# pc_healthypi_move_sensor_dual_v3.net
KiCad netlist of a schematic drawn in EAGLE
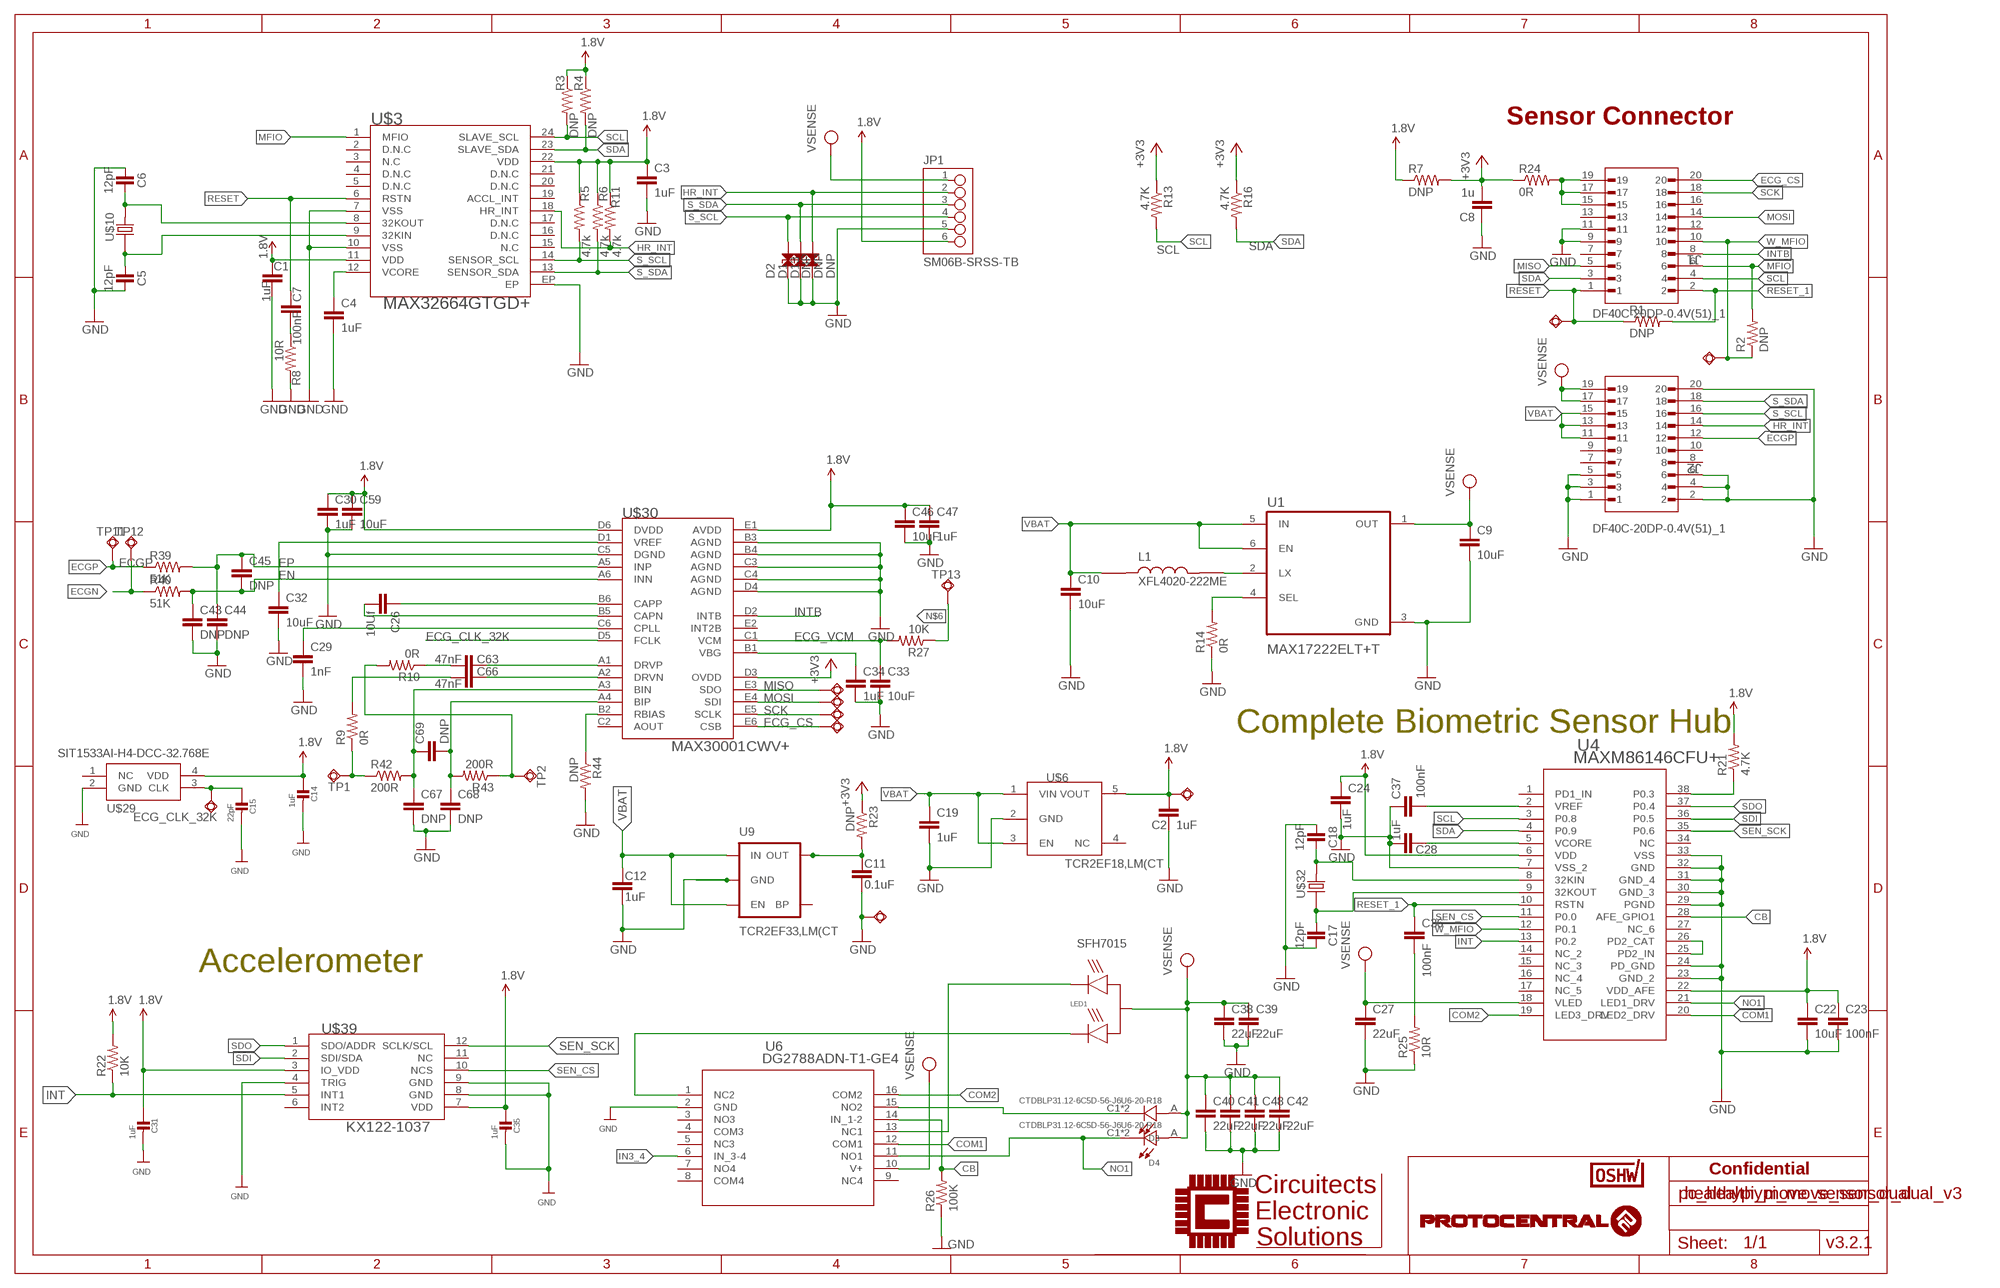
[diagram p0: schematic, sheet 1]

(export (version "E")
  (design (tool "Eeschema 10.0.6"))
  (components
    (comp (ref "C1")
      (value "1uF")
      (footprint "eagle-import:C0402")
      (libsource (lib "eagle-import") (part "C-EUC0402"))
    )
    (comp (ref "C2")
      (value "1uF")
      (footprint "eagle-import:C0402")
      (libsource (lib "eagle-import") (part "C-EUC0402"))
    )
    (comp (ref "C3")
      (value "1uF")
      (footprint "eagle-import:C0402")
      (libsource (lib "eagle-import") (part "C-EUC0402"))
    )
    (comp (ref "C4")
      (value "1uF")
      (footprint "eagle-import:C0402")
      (libsource (lib "eagle-import") (part "C-EUC0402"))
    )
    (comp (ref "C5")
      (value "12pF")
      (footprint "eagle-import:C0402")
      (libsource (lib "eagle-import") (part "CAPACITORS-0402"))
    )
    (comp (ref "C6")
      (value "12pF")
      (footprint "eagle-import:C0402")
      (libsource (lib "eagle-import") (part "CAPACITORS-0402"))
    )
    (comp (ref "C7")
      (value "100nF")
      (footprint "eagle-import:C0402")
      (libsource (lib "eagle-import") (part "C-EUC0402"))
    )
    (comp (ref "C8")
      (value "1u")
      (footprint "eagle-import:C0402")
      (libsource (lib "eagle-import") (part "C-EUC0402"))
    )
    (comp (ref "C9")
      (value "10uF")
      (footprint "eagle-import:C0402")
      (libsource (lib "eagle-import") (part "C-EUC0402"))
    )
    (comp (ref "C10")
      (value "10uF")
      (footprint "eagle-import:C0402")
      (libsource (lib "eagle-import") (part "C-EUC0402"))
    )
    (comp (ref "C11")
      (value "0.1uF")
      (footprint "eagle-import:0402")
      (libsource (lib "eagle-import") (part "0.1UF-0402-16V-10%"))
    )
    (comp (ref "C12")
      (value "1uF")
      (footprint "eagle-import:0402-TIGHT")
      (libsource (lib "eagle-import") (part "0.1UF-0402T-6.3V-10%-X7R"))
    )
    (comp (ref "C14")
      (value "1uF")
      (footprint "eagle-import:0402")
      (libsource (lib "eagle-import") (part "CAP_CERAMIC0402"))
    )
    (comp (ref "C15")
      (value "22pF")
      (footprint "eagle-import:0402")
      (libsource (lib "eagle-import") (part "CAP_CERAMIC0402"))
    )
    (comp (ref "C17")
      (value "12pF")
      (footprint "eagle-import:C0402")
      (libsource (lib "eagle-import") (part "CAPACITORS-0402"))
    )
    (comp (ref "C18")
      (value "12pF")
      (footprint "eagle-import:C0402")
      (libsource (lib "eagle-import") (part "CAPACITORS-0402"))
    )
    (comp (ref "C19")
      (value "1uF")
      (footprint "eagle-import:C0402")
      (libsource (lib "eagle-import") (part "C-EUC0402"))
    )
    (comp (ref "C22")
      (value "10uF")
      (footprint "eagle-import:C0402")
      (libsource (lib "eagle-import") (part "C-EUC0402"))
    )
    (comp (ref "C23")
      (value "100nF")
      (footprint "eagle-import:C0402")
      (libsource (lib "eagle-import") (part "C-EUC0402"))
    )
    (comp (ref "C24")
      (value "1uF")
      (footprint "eagle-import:C0402")
      (libsource (lib "eagle-import") (part "C-EUC0402"))
    )
    (comp (ref "C26")
      (value "10Uf")
      (footprint "eagle-import:C0402")
      (libsource (lib "eagle-import") (part "C-EUC0402"))
    )
    (comp (ref "C27")
      (value "22uF")
      (footprint "eagle-import:C0805")
      (libsource (lib "eagle-import") (part "C-EUC0805"))
    )
    (comp (ref "C28")
      (value "1uF")
      (footprint "eagle-import:C0402")
      (libsource (lib "eagle-import") (part "C-EUC0402"))
    )
    (comp (ref "C29")
      (value "1nF")
      (footprint "eagle-import:C0402")
      (libsource (lib "eagle-import") (part "C-EUC0402"))
    )
    (comp (ref "C30")
      (value "1uF")
      (footprint "eagle-import:C0402")
      (libsource (lib "eagle-import") (part "C-EUC0402"))
    )
    (comp (ref "C31")
      (value "1uF")
      (footprint "eagle-import:0402")
      (libsource (lib "eagle-import") (part "CAP_CERAMIC0402"))
    )
    (comp (ref "C32")
      (value "10uF")
      (footprint "eagle-import:C0402")
      (libsource (lib "eagle-import") (part "C-EUC0402"))
    )
    (comp (ref "C33")
      (value "10uF")
      (footprint "eagle-import:C0402")
      (libsource (lib "eagle-import") (part "C-EUC0402"))
    )
    (comp (ref "C34")
      (value "1uF")
      (footprint "eagle-import:C0402")
      (libsource (lib "eagle-import") (part "C-EUC0402"))
    )
    (comp (ref "C35")
      (value "1uF")
      (footprint "eagle-import:0402")
      (libsource (lib "eagle-import") (part "CAP_CERAMIC0402"))
    )
    (comp (ref "C36")
      (value "100nF")
      (footprint "eagle-import:C0402")
      (libsource (lib "eagle-import") (part "C-EUC0402"))
    )
    (comp (ref "C37")
      (value "100nF")
      (footprint "eagle-import:C0402")
      (libsource (lib "eagle-import") (part "C-EUC0402"))
    )
    (comp (ref "C38")
      (value "22uF")
      (footprint "eagle-import:C0805")
      (libsource (lib "eagle-import") (part "C-EUC0805"))
    )
    (comp (ref "C39")
      (value "22uF")
      (footprint "eagle-import:C0805")
      (libsource (lib "eagle-import") (part "C-EUC0805"))
    )
    (comp (ref "C40")
      (value "22uF")
      (footprint "eagle-import:C0805")
      (libsource (lib "eagle-import") (part "C-EUC0805"))
    )
    (comp (ref "C41")
      (value "22uF")
      (footprint "eagle-import:C0805")
      (libsource (lib "eagle-import") (part "C-EUC0805"))
    )
    (comp (ref "C42")
      (value "22uF")
      (footprint "eagle-import:C0805")
      (libsource (lib "eagle-import") (part "C-EUC0805"))
    )
    (comp (ref "C43")
      (value "DNP")
      (footprint "eagle-import:C0402")
      (libsource (lib "eagle-import") (part "C-EUC0402"))
    )
    (comp (ref "C44")
      (value "DNP")
      (footprint "eagle-import:C0402")
      (libsource (lib "eagle-import") (part "C-EUC0402"))
    )
    (comp (ref "C45")
      (value "DNP")
      (footprint "eagle-import:C0402")
      (libsource (lib "eagle-import") (part "C-EUC0402"))
    )
    (comp (ref "C46")
      (value "10uF")
      (footprint "eagle-import:C0402")
      (libsource (lib "eagle-import") (part "C-EUC0402"))
    )
    (comp (ref "C47")
      (value "1uF")
      (footprint "eagle-import:C0402")
      (libsource (lib "eagle-import") (part "C-EUC0402"))
    )
    (comp (ref "C48")
      (value "22uF")
      (footprint "eagle-import:C0805")
      (libsource (lib "eagle-import") (part "C-EUC0805"))
    )
    (comp (ref "C59")
      (value "10uF")
      (footprint "eagle-import:C0402")
      (libsource (lib "eagle-import") (part "C-EUC0402"))
    )
    (comp (ref "C63")
      (value "47nF")
      (footprint "eagle-import:C0402")
      (libsource (lib "eagle-import") (part "C-EUC0402"))
    )
    (comp (ref "C66")
      (value "47nF")
      (footprint "eagle-import:C0402")
      (libsource (lib "eagle-import") (part "C-EUC0402"))
    )
    (comp (ref "C67")
      (value "DNP")
      (footprint "eagle-import:C0402")
      (libsource (lib "eagle-import") (part "C-EUC0402"))
    )
    (comp (ref "C68")
      (value "DNP")
      (footprint "eagle-import:C0402")
      (libsource (lib "eagle-import") (part "C-EUC0402"))
    )
    (comp (ref "C69")
      (value "DNP")
      (footprint "eagle-import:C0402")
      (libsource (lib "eagle-import") (part "C-EUC0402"))
    )
    (comp (ref "D1")
      (value "DNP")
      (footprint "eagle-import:0402")
      (fields
        (field (name "DIGIKEY_PART") "PESD0402-140CT-ND")
        (field (name "MOUSE_PART") "650-PESD0402-140")
      )
      (libsource (lib "eagle-import") (part "PESD0402-0402"))
    )
    (comp (ref "D2")
      (value "DNP")
      (footprint "eagle-import:0402")
      (fields
        (field (name "DIGIKEY_PART") "PESD0402-140CT-ND")
        (field (name "MOUSE_PART") "650-PESD0402-140")
      )
      (libsource (lib "eagle-import") (part "PESD0402-0402"))
    )
    (comp (ref "D3")
      (value "CTDBLP31.12-6C5D-56-J6U6-20-R18")
      (footprint "eagle-import:LED_CTDBLP31.12-6C5D-56-J6U6-20-R18")
      (fields
        (field (name "MF") "OSRAM Opto Semiconductors")
        (field (name "MP") "CT DBLP31.12-6C5D-56-J6U6-20-R18")
      )
      (libsource (lib "eagle-import") (part "CTDBLP31.12-6C5D-56-J6U6-20-R18"))
    )
    (comp (ref "D4")
      (value "CTDBLP31.12-6C5D-56-J6U6-20-R18")
      (footprint "eagle-import:LED_CTDBLP31.12-6C5D-56-J6U6-20-R18")
      (fields
        (field (name "MF") "OSRAM Opto Semiconductors")
        (field (name "MP") "CT DBLP31.12-6C5D-56-J6U6-20-R18")
      )
      (libsource (lib "eagle-import") (part "CTDBLP31.12-6C5D-56-J6U6-20-R18"))
    )
    (comp (ref "D13")
      (value "DNP")
      (footprint "eagle-import:0402")
      (fields
        (field (name "DIGIKEY_PART") "PESD0402-140CT-ND")
        (field (name "MOUSE_PART") "650-PESD0402-140")
      )
      (libsource (lib "eagle-import") (part "PESD0402-0402"))
    )
    (comp (ref "J1")
      (value "DF40C-20DP-0.4V(51)_1")
      (footprint "eagle-import:HRS_DF40C-20DP-0.4V(51)")
      (fields (field (name "MANUFACTURER") "Hirose Electric"))
      (libsource (lib "eagle-import") (part "DF40C-20DP-0.4V(51)_1"))
    )
    (comp (ref "J2")
      (value "DF40C-20DP-0.4V(51)_1")
      (footprint "eagle-import:HRS_DF40C-20DP-0.4V(51)")
      (fields (field (name "MANUFACTURER") "Hirose Electric"))
      (libsource (lib "eagle-import") (part "DF40C-20DP-0.4V(51)_1"))
    )
    (comp (ref "JP1")
      (value "SM06B-SRSS-TB")
      (footprint "eagle-import:SM06B-SRSS-TB")
      (fields (field (name "MF") "JST Sales"))
      (libsource (lib "eagle-import") (part "SM06B-SRSS-TB"))
    )
    (comp (ref "L1")
      (value "XFL4020-222ME")
      (footprint "eagle-import:IND_XFL4020-222ME")
      (fields (field (name "MF") "Coilcraft"))
      (libsource (lib "eagle-import") (part "XFL4020-222ME"))
    )
    (comp (ref "LED1")
      (value "SFH7015")
      (footprint "eagle-import:SFH7015")
      (fields (field (name "MF") "OSRAM Opto Semiconductors") (field (name "MP") "SFH 7015"))
      (libsource (lib "eagle-import") (part "SFH7015"))
    )
    (comp (ref "R1")
      (value "DNP")
      (footprint "eagle-import:0402-RES")
      (libsource (lib "eagle-import") (part "RESISTOR0402-RES"))
    )
    (comp (ref "R2")
      (value "DNP")
      (footprint "eagle-import:0402-RES")
      (libsource (lib "eagle-import") (part "RESISTOR0402-RES"))
    )
    (comp (ref "R3")
      (value "DNP")
      (footprint "eagle-import:0402-RES")
      (libsource (lib "eagle-import") (part "RESISTOR0402-RES"))
    )
    (comp (ref "R4")
      (value "DNP")
      (footprint "eagle-import:0402-RES")
      (libsource (lib "eagle-import") (part "RESISTOR0402-RES"))
    )
    (comp (ref "R5")
      (value "4.7k")
      (footprint "eagle-import:0402-RES")
      (libsource (lib "eagle-import") (part "RESISTOR0402-RES"))
    )
    (comp (ref "R6")
      (value "4.7k")
      (footprint "eagle-import:0402-RES")
      (libsource (lib "eagle-import") (part "RESISTOR0402-RES"))
    )
    (comp (ref "R7")
      (value "DNP")
      (footprint "eagle-import:0402-RES")
      (libsource (lib "eagle-import") (part "RESISTOR0402-RES"))
    )
    (comp (ref "R8")
      (value "10R")
      (footprint "eagle-import:0402-RES")
      (libsource (lib "eagle-import") (part "RESISTOR0402-RES"))
    )
    (comp (ref "R9")
      (value "0R")
      (footprint "eagle-import:0402-RES")
      (libsource (lib "eagle-import") (part "RESISTOR0402-RES"))
    )
    (comp (ref "R10")
      (value "0R")
      (footprint "eagle-import:0402-RES")
      (libsource (lib "eagle-import") (part "RESISTOR0402-RES"))
    )
    (comp (ref "R11")
      (value "4.7k")
      (footprint "eagle-import:0402-RES")
      (libsource (lib "eagle-import") (part "RESISTOR0402-RES"))
    )
    (comp (ref "R13")
      (value "4.7K")
      (footprint "eagle-import:0402-RES")
      (libsource (lib "eagle-import") (part "RESISTOR0402-RES"))
    )
    (comp (ref "R14")
      (value "0R")
      (footprint "eagle-import:R0402")
      (libsource (lib "eagle-import") (part "R-US_R0402"))
    )
    (comp (ref "R16")
      (value "4.7K")
      (footprint "eagle-import:0402-RES")
      (libsource (lib "eagle-import") (part "RESISTOR0402-RES"))
    )
    (comp (ref "R21")
      (value "4.7K")
      (footprint "eagle-import:R0402")
      (libsource (lib "eagle-import") (part "R-US_R0402"))
    )
    (comp (ref "R22")
      (value "10K")
      (footprint "eagle-import:0402-RES")
      (libsource (lib "eagle-import") (part "RESISTOR0402-RES"))
    )
    (comp (ref "R23")
      (value "DNP")
      (footprint "eagle-import:0402-RES")
      (libsource (lib "eagle-import") (part "RESISTOR0402-RES"))
    )
    (comp (ref "R24")
      (value "0R")
      (footprint "eagle-import:0402-RES")
      (libsource (lib "eagle-import") (part "RESISTOR0402-RES"))
    )
    (comp (ref "R25")
      (value "10R")
      (footprint "eagle-import:R0402")
      (libsource (lib "eagle-import") (part "R-US_R0402"))
    )
    (comp (ref "R26")
      (value "100K")
      (footprint "eagle-import:R0402")
      (libsource (lib "eagle-import") (part "R-US_R0402"))
    )
    (comp (ref "R27")
      (value "10K")
      (footprint "eagle-import:R0402")
      (libsource (lib "eagle-import") (part "R-US_R0402"))
    )
    (comp (ref "R39")
      (value "51K")
      (footprint "eagle-import:0402-RES")
      (libsource (lib "eagle-import") (part "RESISTOR0402-RES"))
    )
    (comp (ref "R40")
      (value "51K")
      (footprint "eagle-import:0402-RES")
      (libsource (lib "eagle-import") (part "RESISTOR0402-RES"))
    )
    (comp (ref "R42")
      (value "200R")
      (footprint "eagle-import:0402-RES")
      (libsource (lib "eagle-import") (part "RESISTOR0402-RES"))
    )
    (comp (ref "R43")
      (value "200R")
      (footprint "eagle-import:0402-RES")
      (libsource (lib "eagle-import") (part "RESISTOR0402-RES"))
    )
    (comp (ref "R44")
      (value "DNP")
      (footprint "eagle-import:0402-RES")
      (libsource (lib "eagle-import") (part "RESISTOR0402-RES"))
    )
    (comp (ref "SWIO1")
      (value "TPSQTP11R")
      (footprint "eagle-import:TP11R")
      (libsource (lib "eagle-import") (part "TPSQTP11R"))
    )
    (comp (ref "SWIO2")
      (value "TPSQTP11R")
      (footprint "eagle-import:TP11R")
      (libsource (lib "eagle-import") (part "TPSQTP11R"))
    )
    (comp (ref "SWIO3")
      (value "TPSQTP11R")
      (footprint "eagle-import:TP11R")
      (libsource (lib "eagle-import") (part "TPSQTP11R"))
    )
    (comp (ref "SWIO4")
      (value "TPSQTP11R")
      (footprint "eagle-import:TP11R")
      (libsource (lib "eagle-import") (part "TPSQTP11R"))
    )
    (comp (ref "SWIO5")
      (value "TPSQTP11R")
      (footprint "eagle-import:TP11R")
      (libsource (lib "eagle-import") (part "TPSQTP11R"))
    )
    (comp (ref "SWIO6")
      (value "TPSQTP11R")
      (footprint "eagle-import:TP11R")
      (libsource (lib "eagle-import") (part "TPSQTP11R"))
    )
    (comp (ref "SWIO7")
      (value "TPSQTP11R")
      (footprint "eagle-import:TP11R")
      (libsource (lib "eagle-import") (part "TPSQTP11R"))
    )
    (comp (ref "SWIO8")
      (value "TPSQTP11R")
      (footprint "eagle-import:TP11R")
      (libsource (lib "eagle-import") (part "TPSQTP11R"))
    )
    (comp (ref "SWIO9")
      (value "TPSQTP11R")
      (footprint "eagle-import:TP11R")
      (libsource (lib "eagle-import") (part "TPSQTP11R"))
    )
    (comp (ref "TP1")
      (value "TPSQTP20SQ")
      (footprint "eagle-import:TP20SQ")
      (libsource (lib "eagle-import") (part "TPSQTP20SQ"))
    )
    (comp (ref "TP2")
      (value "TPSQTP20SQ")
      (footprint "eagle-import:TP20SQ")
      (libsource (lib "eagle-import") (part "TPSQTP20SQ"))
    )
    (comp (ref "TP11")
      (value "TPSQTP20SQ")
      (footprint "eagle-import:TP20SQ")
      (libsource (lib "eagle-import") (part "TPSQTP20SQ"))
    )
    (comp (ref "TP12")
      (value "TPSQTP20SQ")
      (footprint "eagle-import:TP20SQ")
      (libsource (lib "eagle-import") (part "TPSQTP20SQ"))
    )
    (comp (ref "TP13")
      (value "TPSQTP20SQ")
      (footprint "eagle-import:TP20SQ")
      (libsource (lib "eagle-import") (part "TPSQTP20SQ"))
    )
    (comp (ref "U$3")
      (value "MAX32664GTGD+")
      (footprint "eagle-import:TQFN-24L")
      (libsource (lib "eagle-import") (part "MAX32664GTGA+"))
    )
    (comp (ref "U$6")
      (value "TCR2EF18,LM(CT")
      (footprint "eagle-import:SOT95P285X140-5N")
      (libsource (lib "eagle-import") (part "AP7354D-18W5-7"))
    )
    (comp (ref "U$10")
      (value "520-327-12.5-34B(32.768KHZ)")
      (footprint "eagle-import:ECX-31B")
      (libsource (lib "eagle-import") (part "ECS-X-34B"))
    )
    (comp (ref "U$29")
      (value "SIT1533AI-H4-DCC-32.768E")
      (footprint "eagle-import:SIT1533")
      (libsource (lib "eagle-import") (part "SIT1533AI-H4-DCC-32.768E"))
    )
    (comp (ref "U$30")
      (value "MAX30001CWV+")
      (footprint "eagle-import:30WLP")
      (libsource (lib "eagle-import") (part "MAX30001CWV+"))
    )
    (comp (ref "U$32")
      (value "520-327-12.5-34B(32.768KHZ)")
      (footprint "eagle-import:ECX-31B")
      (libsource (lib "eagle-import") (part "ECS-X-34B"))
    )
    (comp (ref "U$39")
      (value "KX122-1037")
      (footprint "eagle-import:KIONIX_KXTJ3-1057")
      (libsource (lib "eagle-import") (part "KX122-1037"))
    )
    (comp (ref "U$48")
      (value "CERT-SMALL")
      (footprint "eagle-import:CERT-SMALL-SILK")
      (libsource (lib "eagle-import") (part "CERT-SMALL"))
    )
    (comp (ref "U1")
      (value "MAX17222ELT+T")
      (footprint "eagle-import:SON65P200X200X80-6N")
      (fields (field (name "MF") "Analog Devices"))
      (libsource (lib "eagle-import") (part "MAX17222ELT+T"))
    )
    (comp (ref "U4")
      (value "MAXM86146CFU+")
      (footprint "eagle-import:21-100323A_90-100112A_MXM")
      (fields (field (name "COPYRIGHT") "Copyright (C) 2023 Ultra Librarian. All rights reserved."))
      (libsource (lib "eagle-import") (part "MAXM86146CFU+"))
    )
    (comp (ref "U6")
      (value "DG2788ADN-T1-GE4")
      (footprint "eagle-import:MINIQFN-16_VIS")
      (fields (field (name "COPYRIGHT") "Copyright (C) 2023 Ultra Librarian. All rights reserved."))
      (libsource (lib "eagle-import") (part "DG2788ADN-T1-GE4"))
    )
    (comp (ref "U9")
      (value "TCR2EF33,LM(CT")
      (footprint "eagle-import:SOT23-5")
      (libsource (lib "eagle-import") (part "V_REG_LDOSMD"))
    )
  )
  (nets
    (net (code "1") (name "+3V3") (class "Default")
      (node (ref "C8") (pin "2") (pinfunction "2_2") (pintype "passive"))
      (node (ref "R13") (pin "1") (pinfunction "1_1") (pintype "passive"))
      (node (ref "R16") (pin "1") (pinfunction "1_1") (pintype "passive"))
      (node (ref "R23") (pin "1") (pinfunction "1_1") (pintype "passive"))
      (node (ref "R24") (pin "1") (pinfunction "1_1") (pintype "passive"))
      (node (ref "R7") (pin "2") (pinfunction "2_2") (pintype "passive"))
      (node (ref "U$30") (pin "D3") (pinfunction "OVDD_D3") (pintype "bidirectional"))
    )
    (net (code "2") (name "/ECG_CLK_32K") (class "Default")
      (node (ref "C15") (pin "1") (pinfunction "P$1_1") (pintype "passive"))
      (node (ref "SWIO1") (pin "TP") (pinfunction "TP_TP") (pintype "input"))
      (node (ref "U$29") (pin "3") (pinfunction "CLK_3") (pintype "bidirectional"))
      (node (ref "U$30") (pin "D5") (pinfunction "FCLK_D5") (pintype "bidirectional"))
    )
    (net (code "3") (name "/ECG_VCM") (class "Default")
      (node (ref "C33") (pin "1") (pinfunction "1_1") (pintype "passive"))
      (node (ref "R27") (pin "2") (pinfunction "2_2") (pintype "passive"))
      (node (ref "U$30") (pin "C1") (pinfunction "VCM_C1") (pintype "bidirectional"))
    )
    (net (code "4") (name "/EN") (class "Default")
      (node (ref "C43") (pin "1") (pinfunction "1_1") (pintype "passive"))
      (node (ref "C45") (pin "2") (pinfunction "2_2") (pintype "passive"))
      (node (ref "R40") (pin "2") (pinfunction "2_2") (pintype "passive"))
      (node (ref "U$30") (pin "A6") (pinfunction "INN_A6") (pintype "bidirectional"))
    )
    (net (code "5") (name "/EP") (class "Default")
      (node (ref "C44") (pin "1") (pinfunction "1_1") (pintype "passive"))
      (node (ref "C45") (pin "1") (pinfunction "1_1") (pintype "passive"))
      (node (ref "R39") (pin "2") (pinfunction "2_2") (pintype "passive"))
      (node (ref "U$30") (pin "A5") (pinfunction "INP_A5") (pintype "bidirectional"))
    )
    (net (code "6") (name "1.8V") (class "Default")
      (node (ref "C1") (pin "1") (pinfunction "1_1") (pintype "passive"))
      (node (ref "C14") (pin "1") (pinfunction "P$1_1") (pintype "passive"))
      (node (ref "C2") (pin "1") (pinfunction "1_1") (pintype "passive"))
      (node (ref "C22") (pin "1") (pinfunction "1_1") (pintype "passive"))
      (node (ref "C23") (pin "1") (pinfunction "1_1") (pintype "passive"))
      (node (ref "C24") (pin "1") (pinfunction "1_1") (pintype "passive"))
      (node (ref "C3") (pin "1") (pinfunction "1_1") (pintype "passive"))
      (node (ref "C30") (pin "1") (pinfunction "1_1") (pintype "passive"))
      (node (ref "C31") (pin "1") (pinfunction "P$1_1") (pintype "passive"))
      (node (ref "C35") (pin "1") (pinfunction "P$1_1") (pintype "passive"))
      (node (ref "C46") (pin "1") (pinfunction "1_1") (pintype "passive"))
      (node (ref "C47") (pin "1") (pinfunction "1_1") (pintype "passive"))
      (node (ref "C59") (pin "1") (pinfunction "1_1") (pintype "passive"))
      (node (ref "JP1") (pin "6") (pinfunction "P$6_6") (pintype "bidirectional"))
      (node (ref "R11") (pin "1") (pinfunction "1_1") (pintype "passive"))
      (node (ref "R21") (pin "2") (pinfunction "2_2") (pintype "passive"))
      (node (ref "R22") (pin "2") (pinfunction "2_2") (pintype "passive"))
      (node (ref "R3") (pin "1") (pinfunction "1_1") (pintype "passive"))
      (node (ref "R4") (pin "1") (pinfunction "1_1") (pintype "passive"))
      (node (ref "R5") (pin "1") (pinfunction "1_1") (pintype "passive"))
      (node (ref "R6") (pin "1") (pinfunction "1_1") (pintype "passive"))
      (node (ref "R7") (pin "1") (pinfunction "1_1") (pintype "passive"))
      (node (ref "SWIO5") (pin "TP") (pinfunction "TP_TP") (pintype "input"))
      (node (ref "U$29") (pin "4") (pinfunction "VDD_4") (pintype "bidirectional"))
      (node (ref "U$3") (pin "11") (pinfunction "VDD_11") (pintype "bidirectional"))
      (node (ref "U$3") (pin "22") (pinfunction "VDD_22") (pintype "bidirectional"))
      (node (ref "U$30") (pin "D6") (pinfunction "DVDD_D6") (pintype "bidirectional"))
      (node (ref "U$30") (pin "E1") (pinfunction "AVDD_E1") (pintype "bidirectional"))
      (node (ref "U$39") (pin "3") (pinfunction "IO_VDD_3") (pintype "bidirectional"))
      (node (ref "U$39") (pin "7") (pinfunction "VDD_7") (pintype "bidirectional"))
      (node (ref "U$6") (pin "5") (pinfunction "VOUT_5") (pintype "bidirectional"))
      (node (ref "U4") (pin "22") (pinfunction "VDD_AFE_22") (pintype "input"))
      (node (ref "U4") (pin "6") (pinfunction "VDD_6") (pintype "power_in"))
    )
    (net (code "7") (name "CB") (class "Default")
      (node (ref "R26") (pin "2") (pinfunction "2_2") (pintype "passive"))
      (node (ref "U4") (pin "28") (pinfunction "AFE_GPIO1_28") (pintype "bidirectional"))
      (node (ref "U6") (pin "14") (pinfunction "IN_1-2_14") (pintype "bidirectional"))
    )
    (net (code "8") (name "COM1") (class "Default")
      (node (ref "U4") (pin "20") (pinfunction "LED2_DRV_20") (pintype "output"))
      (node (ref "U6") (pin "12") (pinfunction "COM1_12") (pintype "bidirectional"))
    )
    (net (code "9") (name "COM2") (class "Default")
      (node (ref "U4") (pin "19") (pinfunction "LED3_DRV_19") (pintype "output"))
      (node (ref "U6") (pin "16") (pinfunction "COM2_16") (pintype "bidirectional"))
    )
    (net (code "10") (name "ECGN") (class "Default")
      (node (ref "R40") (pin "1") (pinfunction "1_1") (pintype "passive"))
      (node (ref "TP12") (pin "TP") (pinfunction "TP_TP") (pintype "input"))
    )
    (net (code "11") (name "ECGP") (class "Default")
      (node (ref "J2") (pin "12") (pinfunction "12_12") (pintype "passive"))
      (node (ref "R39") (pin "1") (pinfunction "1_1") (pintype "passive"))
      (node (ref "TP11") (pin "TP") (pinfunction "TP_TP") (pintype "input"))
    )
    (net (code "12") (name "ECG_CS") (class "Default")
      (node (ref "J1") (pin "20") (pinfunction "20_20") (pintype "passive"))
      (node (ref "SWIO7") (pin "TP") (pinfunction "TP_TP") (pintype "input"))
      (node (ref "U$30") (pin "E6") (pinfunction "CSB_E6") (pintype "bidirectional"))
    )
    (net (code "13") (name "GND") (class "Default")
      (node (ref "C1") (pin "2") (pinfunction "2_2") (pintype "passive"))
      (node (ref "C10") (pin "2") (pinfunction "2_2") (pintype "passive"))
      (node (ref "C11") (pin "2") (pinfunction "2_2") (pintype "passive"))
      (node (ref "C12") (pin "2") (pinfunction "2_2") (pintype "passive"))
      (node (ref "C14") (pin "2") (pinfunction "P$2_2") (pintype "passive"))
      (node (ref "C15") (pin "2") (pinfunction "P$2_2") (pintype "passive"))
      (node (ref "C17") (pin "2") (pinfunction "2_2") (pintype "passive"))
      (node (ref "C18") (pin "1") (pinfunction "1_1") (pintype "passive"))
      (node (ref "C19") (pin "2") (pinfunction "2_2") (pintype "passive"))
      (node (ref "C2") (pin "2") (pinfunction "2_2") (pintype "passive"))
      (node (ref "C22") (pin "2") (pinfunction "2_2") (pintype "passive"))
      (node (ref "C23") (pin "2") (pinfunction "2_2") (pintype "passive"))
      (node (ref "C24") (pin "2") (pinfunction "2_2") (pintype "passive"))
      (node (ref "C27") (pin "2") (pinfunction "2_2") (pintype "passive"))
      (node (ref "C28") (pin "2") (pinfunction "2_2") (pintype "passive"))
      (node (ref "C29") (pin "2") (pinfunction "2_2") (pintype "passive"))
      (node (ref "C3") (pin "2") (pinfunction "2_2") (pintype "passive"))
      (node (ref "C30") (pin "2") (pinfunction "2_2") (pintype "passive"))
      (node (ref "C31") (pin "2") (pinfunction "P$2_2") (pintype "passive"))
      (node (ref "C32") (pin "2") (pinfunction "2_2") (pintype "passive"))
      (node (ref "C33") (pin "2") (pinfunction "2_2") (pintype "passive"))
      (node (ref "C34") (pin "2") (pinfunction "2_2") (pintype "passive"))
      (node (ref "C35") (pin "2") (pinfunction "P$2_2") (pintype "passive"))
      (node (ref "C37") (pin "1") (pinfunction "1_1") (pintype "passive"))
      (node (ref "C38") (pin "2") (pinfunction "2_2") (pintype "passive"))
      (node (ref "C39") (pin "2") (pinfunction "2_2") (pintype "passive"))
      (node (ref "C4") (pin "2") (pinfunction "2_2") (pintype "passive"))
      (node (ref "C40") (pin "2") (pinfunction "2_2") (pintype "passive"))
      (node (ref "C41") (pin "2") (pinfunction "2_2") (pintype "passive"))
      (node (ref "C42") (pin "2") (pinfunction "2_2") (pintype "passive"))
      (node (ref "C43") (pin "2") (pinfunction "2_2") (pintype "passive"))
      (node (ref "C44") (pin "2") (pinfunction "2_2") (pintype "passive"))
      (node (ref "C46") (pin "2") (pinfunction "2_2") (pintype "passive"))
      (node (ref "C47") (pin "2") (pinfunction "2_2") (pintype "passive"))
      (node (ref "C48") (pin "2") (pinfunction "2_2") (pintype "passive"))
      (node (ref "C5") (pin "2") (pinfunction "2_2") (pintype "passive"))
      (node (ref "C59") (pin "2") (pinfunction "2_2") (pintype "passive"))
      (node (ref "C6") (pin "1") (pinfunction "1_1") (pintype "passive"))
      (node (ref "C67") (pin "2") (pinfunction "2_2") (pintype "passive"))
      (node (ref "C68") (pin "2") (pinfunction "2_2") (pintype "passive"))
      (node (ref "C8") (pin "1") (pinfunction "1_1") (pintype "passive"))
      (node (ref "C9") (pin "2") (pinfunction "2_2") (pintype "passive"))
      (node (ref "D1") (pin "1") (pinfunction "1_1") (pintype "bidirectional"))
      (node (ref "D13") (pin "1") (pinfunction "1_1") (pintype "bidirectional"))
      (node (ref "D2") (pin "1") (pinfunction "1_1") (pintype "bidirectional"))
      (node (ref "J1") (pin "11") (pinfunction "11_11") (pintype "passive"))
      (node (ref "J1") (pin "9") (pinfunction "9_9") (pintype "passive"))
      (node (ref "J2") (pin "1") (pinfunction "1_1") (pintype "passive"))
      (node (ref "J2") (pin "2") (pinfunction "2_2") (pintype "passive"))
      (node (ref "J2") (pin "20") (pinfunction "20_20") (pintype "passive"))
      (node (ref "J2") (pin "3") (pinfunction "3_3") (pintype "passive"))
      (node (ref "J2") (pin "4") (pinfunction "4_4") (pintype "passive"))
      (node (ref "J2") (pin "5") (pinfunction "5_5") (pintype "passive"))
      (node (ref "J2") (pin "6") (pinfunction "6_6") (pintype "passive"))
      (node (ref "JP1") (pin "5") (pinfunction "P$5_5") (pintype "bidirectional"))
      (node (ref "R14") (pin "1") (pinfunction "1_1") (pintype "passive"))
      (node (ref "R25") (pin "1") (pinfunction "1_1") (pintype "passive"))
      (node (ref "R26") (pin "1") (pinfunction "1_1") (pintype "passive"))
      (node (ref "R44") (pin "2") (pinfunction "2_2") (pintype "passive"))
      (node (ref "R8") (pin "2") (pinfunction "2_2") (pintype "passive"))
      (node (ref "SWIO6") (pin "TP") (pinfunction "TP_TP") (pintype "input"))
      (node (ref "U$29") (pin "2") (pinfunction "GND_2") (pintype "bidirectional"))
      (node (ref "U$3") (pin "10") (pinfunction "VSS_10") (pintype "bidirectional"))
      (node (ref "U$3") (pin "7") (pinfunction "VSS_7") (pintype "bidirectional"))
      (node (ref "U$3") (pin "EP") (pinfunction "EP_EP") (pintype "bidirectional"))
      (node (ref "U$30") (pin "B3") (pinfunction "AGND_B3") (pintype "bidirectional"))
      (node (ref "U$30") (pin "B4") (pinfunction "AGND_B4") (pintype "bidirectional"))
      (node (ref "U$30") (pin "C3") (pinfunction "AGND_C3") (pintype "bidirectional"))
      (node (ref "U$30") (pin "C4") (pinfunction "AGND_C4") (pintype "bidirectional"))
      (node (ref "U$30") (pin "C5") (pinfunction "DGND_C5") (pintype "bidirectional"))
      (node (ref "U$30") (pin "D4") (pinfunction "AGND_D4") (pintype "bidirectional"))
      (node (ref "U$39") (pin "4") (pinfunction "TRIG_4") (pintype "bidirectional"))
      (node (ref "U$39") (pin "8") (pinfunction "GND_8") (pintype "bidirectional"))
      (node (ref "U$39") (pin "9") (pinfunction "GND_9") (pintype "bidirectional"))
      (node (ref "U$6") (pin "2") (pinfunction "GND_2") (pintype "bidirectional"))
      (node (ref "U1") (pin "3") (pinfunction "GND_3") (pintype "power_in"))
      (node (ref "U4") (pin "23") (pinfunction "GND_2_23") (pintype "power_in"))
      (node (ref "U4") (pin "24") (pinfunction "PD_GND_24") (pintype "passive"))
      (node (ref "U4") (pin "29") (pinfunction "PGND_29") (pintype "power_in"))
      (node (ref "U4") (pin "30") (pinfunction "GND_3_30") (pintype "power_in"))
      (node (ref "U4") (pin "31") (pinfunction "GND_4_31") (pintype "power_in"))
      (node (ref "U4") (pin "32") (pinfunction "GND_32") (pintype "power_in"))
      (node (ref "U4") (pin "33") (pinfunction "VSS_33") (pintype "power_in"))
      (node (ref "U4") (pin "7") (pinfunction "VSS_2_7") (pintype "power_in"))
      (node (ref "U6") (pin "2") (pinfunction "GND_2") (pintype "passive"))
      (node (ref "U9") (pin "2") (pinfunction "GND_2") (pintype "input"))
    )
    (net (code "14") (name "HR_INT") (class "Default")
      (node (ref "D13") (pin "2") (pinfunction "2_2") (pintype "bidirectional"))
      (node (ref "J2") (pin "14") (pinfunction "14_14") (pintype "passive"))
      (node (ref "JP1") (pin "2") (pinfunction "P$2_2") (pintype "bidirectional"))
      (node (ref "R11") (pin "2") (pinfunction "2_2") (pintype "passive"))
      (node (ref "U$3") (pin "18") (pinfunction "HR_INT_18") (pintype "bidirectional"))
    )
    (net (code "15") (name "IN3_4") (class "Default")
      (node (ref "U6") (pin "6") (pinfunction "IN_3-4_6") (pintype "bidirectional"))
    )
    (net (code "16") (name "INT") (class "Default")
      (node (ref "R22") (pin "1") (pinfunction "1_1") (pintype "passive"))
      (node (ref "U$39") (pin "5") (pinfunction "INT1_5") (pintype "bidirectional"))
      (node (ref "U4") (pin "13") (pinfunction "P0.2_13") (pintype "passive"))
    )
    (net (code "17") (name "INTB") (class "Default")
      (node (ref "J1") (pin "8") (pinfunction "8_8") (pintype "passive"))
      (node (ref "U$30") (pin "D2") (pinfunction "INTB_D2") (pintype "bidirectional"))
    )
    (net (code "18") (name "MFIO") (class "Default")
      (node (ref "J1") (pin "6") (pinfunction "6_6") (pintype "passive"))
      (node (ref "R2") (pin "2") (pinfunction "2_2") (pintype "passive"))
      (node (ref "U$3") (pin "1") (pinfunction "MFIO_1") (pintype "bidirectional"))
    )
    (net (code "19") (name "MISO") (class "Default")
      (node (ref "J1") (pin "5") (pinfunction "5_5") (pintype "passive"))
      (node (ref "SWIO2") (pin "TP") (pinfunction "TP_TP") (pintype "input"))
      (node (ref "U$30") (pin "E3") (pinfunction "SDO_E3") (pintype "bidirectional"))
    )
    (net (code "20") (name "MOSI") (class "Default")
      (node (ref "J1") (pin "14") (pinfunction "14_14") (pintype "passive"))
      (node (ref "SWIO3") (pin "TP") (pinfunction "TP_TP") (pintype "input"))
      (node (ref "U$30") (pin "E4") (pinfunction "SDI_E4") (pintype "bidirectional"))
    )
    (net (code "21") (name "N$6") (class "Default")
      (node (ref "R27") (pin "1") (pinfunction "1_1") (pintype "passive"))
      (node (ref "TP13") (pin "TP") (pinfunction "TP_TP") (pintype "input"))
    )
    (net (code "22") (name "NO1") (class "Default")
      (node (ref "D4") (pin "C1") (pinfunction "C_C1") (pintype "passive"))
      (node (ref "D4") (pin "C2") (pinfunction "C_C2") (pintype "passive"))
      (node (ref "U4") (pin "21") (pinfunction "LED1_DRV_21") (pintype "output"))
      (node (ref "U6") (pin "11") (pinfunction "NO1_11") (pintype "bidirectional"))
    )
    (net (code "23") (name "Net-(C7-Pad2)") (class "Default")
      (node (ref "C7") (pin "2") (pinfunction "2_2") (pintype "passive"))
      (node (ref "R8") (pin "1") (pinfunction "1_1") (pintype "passive"))
    )
    (net (code "24") (name "Net-(C36-Pad2)") (class "Default")
      (node (ref "C36") (pin "2") (pinfunction "2_2") (pintype "passive"))
      (node (ref "R25") (pin "2") (pinfunction "2_2") (pintype "passive"))
    )
    (net (code "25") (name "Net-(C63-Pad1)") (class "Default")
      (node (ref "C63") (pin "1") (pinfunction "1_1") (pintype "passive"))
      (node (ref "R10") (pin "1") (pinfunction "1_1") (pintype "passive"))
    )
    (net (code "26") (name "Net-(C66-Pad1)") (class "Default")
      (node (ref "C66") (pin "1") (pinfunction "1_1") (pintype "passive"))
      (node (ref "R9") (pin "2") (pinfunction "2_2") (pintype "passive"))
    )
    (net (code "27") (name "Net-(J1-Pad15)") (class "Default")
      (node (ref "J1") (pin "15") (pinfunction "15_15") (pintype "passive"))
      (node (ref "J1") (pin "17") (pinfunction "17_17") (pintype "passive"))
      (node (ref "J1") (pin "19") (pinfunction "19_19") (pintype "passive"))
      (node (ref "R24") (pin "2") (pinfunction "2_2") (pintype "passive"))
    )
    (net (code "28") (name "Net-(LED1-IRC)") (class "Default")
      (node (ref "LED1") (pin "4") (pinfunction "IRC_4") (pintype "passive"))
      (node (ref "U6") (pin "13") (pinfunction "NC1_13") (pintype "bidirectional"))
    )
    (net (code "29") (name "Net-(LED1-RC)") (class "Default")
      (node (ref "LED1") (pin "2") (pinfunction "RC_2") (pintype "passive"))
      (node (ref "U6") (pin "1") (pinfunction "NC2_1") (pintype "bidirectional"))
    )
    (net (code "30") (name "Net-(R10-Pad2)") (class "Default")
      (node (ref "R10") (pin "2") (pinfunction "2_2") (pintype "passive"))
      (node (ref "R43") (pin "1") (pinfunction "1_1") (pintype "passive"))
      (node (ref "TP2") (pin "TP") (pinfunction "TP_TP") (pintype "input"))
    )
    (net (code "31") (name "Net-(R42-Pad1)") (class "Default")
      (node (ref "R42") (pin "1") (pinfunction "1_1") (pintype "passive"))
      (node (ref "R9") (pin "1") (pinfunction "1_1") (pintype "passive"))
      (node (ref "TP1") (pin "TP") (pinfunction "TP_TP") (pintype "input"))
    )
    (net (code "32") (name "Net-(U$3-VCORE)") (class "Default")
      (node (ref "C4") (pin "1") (pinfunction "1_1") (pintype "passive"))
      (node (ref "U$3") (pin "12") (pinfunction "VCORE_12") (pintype "bidirectional"))
    )
    (net (code "33") (name "Net-(U$10-1)") (class "Default")
      (node (ref "C5") (pin "1") (pinfunction "1_1") (pintype "passive"))
      (node (ref "U$10") (pin "P$1") (pinfunction "1_P$1") (pintype "passive"))
      (node (ref "U$3") (pin "9") (pinfunction "32KIN_9") (pintype "bidirectional"))
    )
    (net (code "34") (name "Net-(U$10-2)") (class "Default")
      (node (ref "C6") (pin "2") (pinfunction "2_2") (pintype "passive"))
      (node (ref "U$10") (pin "P$2") (pinfunction "2_P$2") (pintype "passive"))
      (node (ref "U$3") (pin "8") (pinfunction "32KOUT_8") (pintype "bidirectional"))
    )
    (net (code "35") (name "Net-(U$30-BIN)") (class "Default")
      (node (ref "C67") (pin "1") (pinfunction "1_1") (pintype "passive"))
      (node (ref "C69") (pin "1") (pinfunction "1_1") (pintype "passive"))
      (node (ref "R42") (pin "2") (pinfunction "2_2") (pintype "passive"))
      (node (ref "U$30") (pin "A3") (pinfunction "BIN_A3") (pintype "bidirectional"))
    )
    (net (code "36") (name "Net-(U$30-BIP)") (class "Default")
      (node (ref "C68") (pin "1") (pinfunction "1_1") (pintype "passive"))
      (node (ref "C69") (pin "2") (pinfunction "2_2") (pintype "passive"))
      (node (ref "R43") (pin "2") (pinfunction "2_2") (pintype "passive"))
      (node (ref "U$30") (pin "A4") (pinfunction "BIP_A4") (pintype "bidirectional"))
    )
    (net (code "37") (name "Net-(U$30-CAPN)") (class "Default")
      (node (ref "C26") (pin "2") (pinfunction "2_2") (pintype "passive"))
      (node (ref "U$30") (pin "B5") (pinfunction "CAPN_B5") (pintype "bidirectional"))
    )
    (net (code "38") (name "Net-(U$30-CAPP)") (class "Default")
      (node (ref "C26") (pin "1") (pinfunction "1_1") (pintype "passive"))
      (node (ref "U$30") (pin "B6") (pinfunction "CAPP_B6") (pintype "bidirectional"))
    )
    (net (code "39") (name "Net-(U$30-CPLL)") (class "Default")
      (node (ref "C29") (pin "1") (pinfunction "1_1") (pintype "passive"))
      (node (ref "U$30") (pin "C6") (pinfunction "CPLL_C6") (pintype "bidirectional"))
    )
    (net (code "40") (name "Net-(U$30-DRVN)") (class "Default")
      (node (ref "C66") (pin "2") (pinfunction "2_2") (pintype "passive"))
      (node (ref "U$30") (pin "A2") (pinfunction "DRVN_A2") (pintype "bidirectional"))
    )
    (net (code "41") (name "Net-(U$30-DRVP)") (class "Default")
      (node (ref "C63") (pin "2") (pinfunction "2_2") (pintype "passive"))
      (node (ref "U$30") (pin "A1") (pinfunction "DRVP_A1") (pintype "bidirectional"))
    )
    (net (code "42") (name "Net-(U$30-RBIAS)") (class "Default")
      (node (ref "R44") (pin "1") (pinfunction "1_1") (pintype "passive"))
      (node (ref "U$30") (pin "B2") (pinfunction "RBIAS_B2") (pintype "bidirectional"))
    )
    (net (code "43") (name "Net-(U$30-VBG)") (class "Default")
      (node (ref "C34") (pin "1") (pinfunction "1_1") (pintype "passive"))
      (node (ref "U$30") (pin "B1") (pinfunction "VBG_B1") (pintype "bidirectional"))
    )
    (net (code "44") (name "Net-(U$30-VREF)") (class "Default")
      (node (ref "C32") (pin "1") (pinfunction "1_1") (pintype "passive"))
      (node (ref "U$30") (pin "D1") (pinfunction "VREF_D1") (pintype "bidirectional"))
    )
    (net (code "45") (name "Net-(U$32-1)") (class "Default")
      (node (ref "C17") (pin "1") (pinfunction "1_1") (pintype "passive"))
      (node (ref "U$32") (pin "P$1") (pinfunction "1_P$1") (pintype "passive"))
      (node (ref "U4") (pin "9") (pinfunction "32KOUT_9") (pintype "output"))
    )
    (net (code "46") (name "Net-(U$32-2)") (class "Default")
      (node (ref "C18") (pin "2") (pinfunction "2_2") (pintype "passive"))
      (node (ref "U$32") (pin "P$2") (pinfunction "2_P$2") (pintype "passive"))
      (node (ref "U4") (pin "8") (pinfunction "32KIN_8") (pintype "input"))
    )
    (net (code "47") (name "Net-(U1-LX)") (class "Default")
      (node (ref "L1") (pin "2") (pinfunction "2_2") (pintype "passive"))
      (node (ref "U1") (pin "2") (pinfunction "LX_2") (pintype "bidirectional"))
    )
    (net (code "48") (name "Net-(U1-SEL)") (class "Default")
      (node (ref "R14") (pin "2") (pinfunction "2_2") (pintype "passive"))
      (node (ref "U1") (pin "4") (pinfunction "SEL_4") (pintype "bidirectional"))
    )
    (net (code "49") (name "Net-(U4-P0.3)") (class "Default")
      (node (ref "R21") (pin "1") (pinfunction "1_1") (pintype "passive"))
      (node (ref "U4") (pin "38") (pinfunction "P0.3_38") (pintype "input"))
    )
    (net (code "50") (name "Net-(U4-PD2_CAT)") (class "Default")
      (node (ref "U4") (pin "25") (pinfunction "PD2_IN_25") (pintype "input"))
      (node (ref "U4") (pin "26") (pinfunction "PD2_CAT_26") (pintype "passive"))
    )
    (net (code "51") (name "Net-(U4-VCORE)") (class "Default")
      (node (ref "C28") (pin "1") (pinfunction "1_1") (pintype "passive"))
      (node (ref "U4") (pin "5") (pinfunction "VCORE_5") (pintype "power_in"))
    )
    (net (code "52") (name "Net-(U4-VREF)") (class "Default")
      (node (ref "C37") (pin "2") (pinfunction "2_2") (pintype "passive"))
      (node (ref "U4") (pin "2") (pinfunction "VREF_2") (pintype "passive"))
    )
    (net (code "53") (name "Net-(U6-NO2)") (class "Default")
      (node (ref "D3") (pin "C1") (pinfunction "C_C1") (pintype "passive"))
      (node (ref "D3") (pin "C2") (pinfunction "C_C2") (pintype "passive"))
      (node (ref "U6") (pin "15") (pinfunction "NO2_15") (pintype "bidirectional"))
    )
    (net (code "54") (name "Net-(U9-OUT)") (class "Default")
      (node (ref "C11") (pin "1") (pinfunction "1_1") (pintype "passive"))
      (node (ref "R23") (pin "2") (pinfunction "2_2") (pintype "passive"))
      (node (ref "U9") (pin "5") (pinfunction "OUT_5") (pintype "passive"))
    )
    (net (code "55") (name "RESET") (class "Default")
      (node (ref "C7") (pin "1") (pinfunction "1_1") (pintype "passive"))
      (node (ref "J1") (pin "1") (pinfunction "1_1") (pintype "passive"))
      (node (ref "R1") (pin "1") (pinfunction "1_1") (pintype "passive"))
      (node (ref "SWIO8") (pin "TP") (pinfunction "TP_TP") (pintype "input"))
      (node (ref "U$3") (pin "6") (pinfunction "RSTN_6") (pintype "bidirectional"))
    )
    (net (code "56") (name "RESET_1") (class "Default")
      (node (ref "C36") (pin "1") (pinfunction "1_1") (pintype "passive"))
      (node (ref "J1") (pin "2") (pinfunction "2_2") (pintype "passive"))
      (node (ref "R1") (pin "2") (pinfunction "2_2") (pintype "passive"))
      (node (ref "U4") (pin "10") (pinfunction "RSTN_10") (pintype "input"))
    )
    (net (code "57") (name "SCK") (class "Default")
      (node (ref "J1") (pin "18") (pinfunction "18_18") (pintype "passive"))
      (node (ref "SWIO4") (pin "TP") (pinfunction "TP_TP") (pintype "input"))
      (node (ref "U$30") (pin "E5") (pinfunction "SCLK_E5") (pintype "bidirectional"))
    )
    (net (code "58") (name "SCL") (class "Default")
      (node (ref "J1") (pin "4") (pinfunction "4_4") (pintype "passive"))
      (node (ref "R13") (pin "2") (pinfunction "2_2") (pintype "passive"))
      (node (ref "R3") (pin "2") (pinfunction "2_2") (pintype "passive"))
      (node (ref "U$3") (pin "24") (pinfunction "SLAVE_SCL_24") (pintype "bidirectional"))
      (node (ref "U4") (pin "3") (pinfunction "P0.8_3") (pintype "passive"))
    )
    (net (code "59") (name "SDA") (class "Default")
      (node (ref "J1") (pin "3") (pinfunction "3_3") (pintype "passive"))
      (node (ref "R16") (pin "2") (pinfunction "2_2") (pintype "passive"))
      (node (ref "R4") (pin "2") (pinfunction "2_2") (pintype "passive"))
      (node (ref "U$3") (pin "23") (pinfunction "SLAVE_SDA_23") (pintype "bidirectional"))
      (node (ref "U4") (pin "4") (pinfunction "P0.9_4") (pintype "passive"))
    )
    (net (code "60") (name "SDI") (class "Default")
      (node (ref "U$39") (pin "2") (pinfunction "SDI/SDA_2") (pintype "bidirectional"))
      (node (ref "U4") (pin "36") (pinfunction "P0.5_36") (pintype "bidirectional"))
    )
    (net (code "61") (name "SDO") (class "Default")
      (node (ref "U$39") (pin "1") (pinfunction "SDO/ADDR_1") (pintype "bidirectional"))
      (node (ref "U4") (pin "37") (pinfunction "P0.4_37") (pintype "bidirectional"))
    )
    (net (code "62") (name "SEN_CS") (class "Default")
      (node (ref "U$39") (pin "10") (pinfunction "NCS_10") (pintype "bidirectional"))
      (node (ref "U4") (pin "11") (pinfunction "P0.0_11") (pintype "passive"))
    )
    (net (code "63") (name "SEN_SCK") (class "Default")
      (node (ref "U$39") (pin "12") (pinfunction "SCLK/SCL_12") (pintype "bidirectional"))
      (node (ref "U4") (pin "35") (pinfunction "P0.6_35") (pintype "bidirectional"))
    )
    (net (code "64") (name "S_SCL") (class "Default")
      (node (ref "D2") (pin "2") (pinfunction "2_2") (pintype "bidirectional"))
      (node (ref "J2") (pin "16") (pinfunction "16_16") (pintype "passive"))
      (node (ref "JP1") (pin "4") (pinfunction "P$4_4") (pintype "bidirectional"))
      (node (ref "R5") (pin "2") (pinfunction "2_2") (pintype "passive"))
      (node (ref "U$3") (pin "14") (pinfunction "SENSOR_SCL_14") (pintype "bidirectional"))
    )
    (net (code "65") (name "S_SDA") (class "Default")
      (node (ref "D1") (pin "2") (pinfunction "2_2") (pintype "bidirectional"))
      (node (ref "J2") (pin "18") (pinfunction "18_18") (pintype "passive"))
      (node (ref "JP1") (pin "3") (pinfunction "P$3_3") (pintype "bidirectional"))
      (node (ref "R6") (pin "2") (pinfunction "2_2") (pintype "passive"))
      (node (ref "U$3") (pin "13") (pinfunction "SENSOR_SDA_13") (pintype "bidirectional"))
    )
    (net (code "66") (name "VBAT") (class "Default")
      (node (ref "C10") (pin "1") (pinfunction "1_1") (pintype "passive"))
      (node (ref "C12") (pin "1") (pinfunction "1_1") (pintype "passive"))
      (node (ref "C19") (pin "1") (pinfunction "1_1") (pintype "passive"))
      (node (ref "J2") (pin "11") (pinfunction "11_11") (pintype "passive"))
      (node (ref "J2") (pin "13") (pinfunction "13_13") (pintype "passive"))
      (node (ref "J2") (pin "15") (pinfunction "15_15") (pintype "passive"))
      (node (ref "L1") (pin "1") (pinfunction "1_1") (pintype "passive"))
      (node (ref "U$6") (pin "1") (pinfunction "VIN_1") (pintype "bidirectional"))
      (node (ref "U$6") (pin "3") (pinfunction "EN_3") (pintype "bidirectional"))
      (node (ref "U1") (pin "5") (pinfunction "IN_5") (pintype "input"))
      (node (ref "U1") (pin "6") (pinfunction "EN_6") (pintype "bidirectional"))
      (node (ref "U9") (pin "1") (pinfunction "IN_1") (pintype "input"))
      (node (ref "U9") (pin "3") (pinfunction "EN_3") (pintype "input"))
    )
    (net (code "67") (name "VSENSE") (class "Default")
      (node (ref "C27") (pin "1") (pinfunction "1_1") (pintype "passive"))
      (node (ref "C38") (pin "1") (pinfunction "1_1") (pintype "passive"))
      (node (ref "C39") (pin "1") (pinfunction "1_1") (pintype "passive"))
      (node (ref "C40") (pin "1") (pinfunction "1_1") (pintype "passive"))
      (node (ref "C41") (pin "1") (pinfunction "1_1") (pintype "passive"))
      (node (ref "C42") (pin "1") (pinfunction "1_1") (pintype "passive"))
      (node (ref "C48") (pin "1") (pinfunction "1_1") (pintype "passive"))
      (node (ref "C9") (pin "1") (pinfunction "1_1") (pintype "passive"))
      (node (ref "D3") (pin "A") (pinfunction "A_A") (pintype "passive"))
      (node (ref "D4") (pin "A") (pinfunction "A_A") (pintype "passive"))
      (node (ref "J2") (pin "17") (pinfunction "17_17") (pintype "passive"))
      (node (ref "J2") (pin "19") (pinfunction "19_19") (pintype "passive"))
      (node (ref "JP1") (pin "1") (pinfunction "P$1_1") (pintype "bidirectional"))
      (node (ref "LED1") (pin "3") (pinfunction "A_3") (pintype "passive"))
      (node (ref "U1") (pin "1") (pinfunction "OUT_1") (pintype "output"))
      (node (ref "U4") (pin "18") (pinfunction "VLED_18") (pintype "input"))
      (node (ref "U6") (pin "10") (pinfunction "V+_10") (pintype "power_in"))
    )
    (net (code "68") (name "W_MFIO") (class "Default")
      (node (ref "J1") (pin "10") (pinfunction "10_10") (pintype "passive"))
      (node (ref "R2") (pin "1") (pinfunction "1_1") (pintype "passive"))
      (node (ref "SWIO9") (pin "TP") (pinfunction "TP_TP") (pintype "input"))
      (node (ref "U4") (pin "12") (pinfunction "P0.1_12") (pintype "passive"))
    )
    (net (code "69") (name "unconnected-(J1-Pad7)") (class "Default")
      (node (ref "J1") (pin "7") (pinfunction "7_7") (pintype "passive"))
    )
    (net (code "70") (name "unconnected-(J1-Pad12)") (class "Default")
      (node (ref "J1") (pin "12") (pinfunction "12_12") (pintype "passive"))
    )
    (net (code "71") (name "unconnected-(J1-Pad13)") (class "Default")
      (node (ref "J1") (pin "13") (pinfunction "13_13") (pintype "passive"))
    )
    (net (code "72") (name "unconnected-(J1-Pad16)") (class "Default")
      (node (ref "J1") (pin "16") (pinfunction "16_16") (pintype "passive"))
    )
    (net (code "73") (name "unconnected-(J2-Pad7)") (class "Default")
      (node (ref "J2") (pin "7") (pinfunction "7_7") (pintype "passive"))
    )
    (net (code "74") (name "unconnected-(J2-Pad8)") (class "Default")
      (node (ref "J2") (pin "8") (pinfunction "8_8") (pintype "passive"))
    )
    (net (code "75") (name "unconnected-(J2-Pad9)") (class "Default")
      (node (ref "J2") (pin "9") (pinfunction "9_9") (pintype "passive"))
    )
    (net (code "76") (name "unconnected-(J2-Pad10)") (class "Default")
      (node (ref "J2") (pin "10") (pinfunction "10_10") (pintype "passive"))
    )
    (net (code "77") (name "unconnected-(U$3-ACCL_INT-Pad19)") (class "Default")
      (node (ref "U$3") (pin "19") (pinfunction "ACCL_INT_19") (pintype "bidirectional"))
    )
    (net (code "78") (name "unconnected-(U$3-D.N.C-Pad2)") (class "Default")
      (node (ref "U$3") (pin "2") (pinfunction "D.N.C_2") (pintype "bidirectional"))
    )
    (net (code "79") (name "unconnected-(U$3-D.N.C-Pad4)") (class "Default")
      (node (ref "U$3") (pin "4") (pinfunction "D.N.C_4") (pintype "bidirectional"))
    )
    (net (code "80") (name "unconnected-(U$3-D.N.C-Pad5)") (class "Default")
      (node (ref "U$3") (pin "5") (pinfunction "D.N.C_5") (pintype "bidirectional"))
    )
    (net (code "81") (name "unconnected-(U$3-D.N.C-Pad16)") (class "Default")
      (node (ref "U$3") (pin "16") (pinfunction "D.N.C_16") (pintype "bidirectional"))
    )
    (net (code "82") (name "unconnected-(U$3-D.N.C-Pad17)") (class "Default")
      (node (ref "U$3") (pin "17") (pinfunction "D.N.C_17") (pintype "bidirectional"))
    )
    (net (code "83") (name "unconnected-(U$3-D.N.C-Pad20)") (class "Default")
      (node (ref "U$3") (pin "20") (pinfunction "D.N.C_20") (pintype "bidirectional"))
    )
    (net (code "84") (name "unconnected-(U$3-D.N.C-Pad21)") (class "Default")
      (node (ref "U$3") (pin "21") (pinfunction "D.N.C_21") (pintype "bidirectional"))
    )
    (net (code "85") (name "unconnected-(U$3-N.C-Pad3)") (class "Default")
      (node (ref "U$3") (pin "3") (pinfunction "N.C_3") (pintype "bidirectional"))
    )
    (net (code "86") (name "unconnected-(U$3-N.C-Pad15)") (class "Default")
      (node (ref "U$3") (pin "15") (pinfunction "N.C_15") (pintype "bidirectional"))
    )
    (net (code "87") (name "unconnected-(U$6-NC-Pad4)") (class "Default")
      (node (ref "U$6") (pin "4") (pinfunction "NC_4") (pintype "bidirectional"))
    )
    (net (code "88") (name "unconnected-(U$29-NC-Pad1)") (class "Default")
      (node (ref "U$29") (pin "1") (pinfunction "NC_1") (pintype "bidirectional"))
    )
    (net (code "89") (name "unconnected-(U$30-AOUT-PadC2)") (class "Default")
      (node (ref "U$30") (pin "C2") (pinfunction "AOUT_C2") (pintype "bidirectional"))
    )
    (net (code "90") (name "unconnected-(U$30-INT2B-PadE2)") (class "Default")
      (node (ref "U$30") (pin "E2") (pinfunction "INT2B_E2") (pintype "bidirectional"))
    )
    (net (code "91") (name "unconnected-(U$39-INT2-Pad6)") (class "Default")
      (node (ref "U$39") (pin "6") (pinfunction "INT2_6") (pintype "bidirectional"))
    )
    (net (code "92") (name "unconnected-(U$39-NC-Pad11)") (class "Default")
      (node (ref "U$39") (pin "11") (pinfunction "NC_11") (pintype "bidirectional"))
    )
    (net (code "93") (name "unconnected-(U4-NC-Pad34)") (class "Default")
      (node (ref "U4") (pin "34") (pinfunction "NC_34") (pintype "passive"))
    )
    (net (code "94") (name "unconnected-(U4-NC_2-Pad14)") (class "Default")
      (node (ref "U4") (pin "14") (pinfunction "NC_2_14") (pintype "passive"))
    )
    (net (code "95") (name "unconnected-(U4-NC_3-Pad15)") (class "Default")
      (node (ref "U4") (pin "15") (pinfunction "NC_3_15") (pintype "passive"))
    )
    (net (code "96") (name "unconnected-(U4-NC_4-Pad16)") (class "Default")
      (node (ref "U4") (pin "16") (pinfunction "NC_4_16") (pintype "passive"))
    )
    (net (code "97") (name "unconnected-(U4-NC_5-Pad17)") (class "Default")
      (node (ref "U4") (pin "17") (pinfunction "NC_5_17") (pintype "passive"))
    )
    (net (code "98") (name "unconnected-(U4-NC_6-Pad27)") (class "Default")
      (node (ref "U4") (pin "27") (pinfunction "NC_6_27") (pintype "passive"))
    )
    (net (code "99") (name "unconnected-(U4-PD1_IN-Pad1)") (class "Default")
      (node (ref "U4") (pin "1") (pinfunction "PD1_IN_1") (pintype "input"))
    )
    (net (code "100") (name "unconnected-(U6-COM3-Pad4)") (class "Default")
      (node (ref "U6") (pin "4") (pinfunction "COM3_4") (pintype "bidirectional"))
    )
    (net (code "101") (name "unconnected-(U6-COM4-Pad8)") (class "Default")
      (node (ref "U6") (pin "8") (pinfunction "COM4_8") (pintype "bidirectional"))
    )
    (net (code "102") (name "unconnected-(U6-NC3-Pad5)") (class "Default")
      (node (ref "U6") (pin "5") (pinfunction "NC3_5") (pintype "bidirectional"))
    )
    (net (code "103") (name "unconnected-(U6-NC4-Pad9)") (class "Default")
      (node (ref "U6") (pin "9") (pinfunction "NC4_9") (pintype "bidirectional"))
    )
    (net (code "104") (name "unconnected-(U6-NO3-Pad3)") (class "Default")
      (node (ref "U6") (pin "3") (pinfunction "NO3_3") (pintype "bidirectional"))
    )
    (net (code "105") (name "unconnected-(U6-NO4-Pad7)") (class "Default")
      (node (ref "U6") (pin "7") (pinfunction "NO4_7") (pintype "bidirectional"))
    )
    (net (code "106") (name "unconnected-(U9-BP-Pad4)") (class "Default")
      (node (ref "U9") (pin "4") (pinfunction "BP_4") (pintype "input"))
    )
  )
)
